# c64-uni-cart-rev4.net
KiCad netlist of a schematic drawn in EAGLE
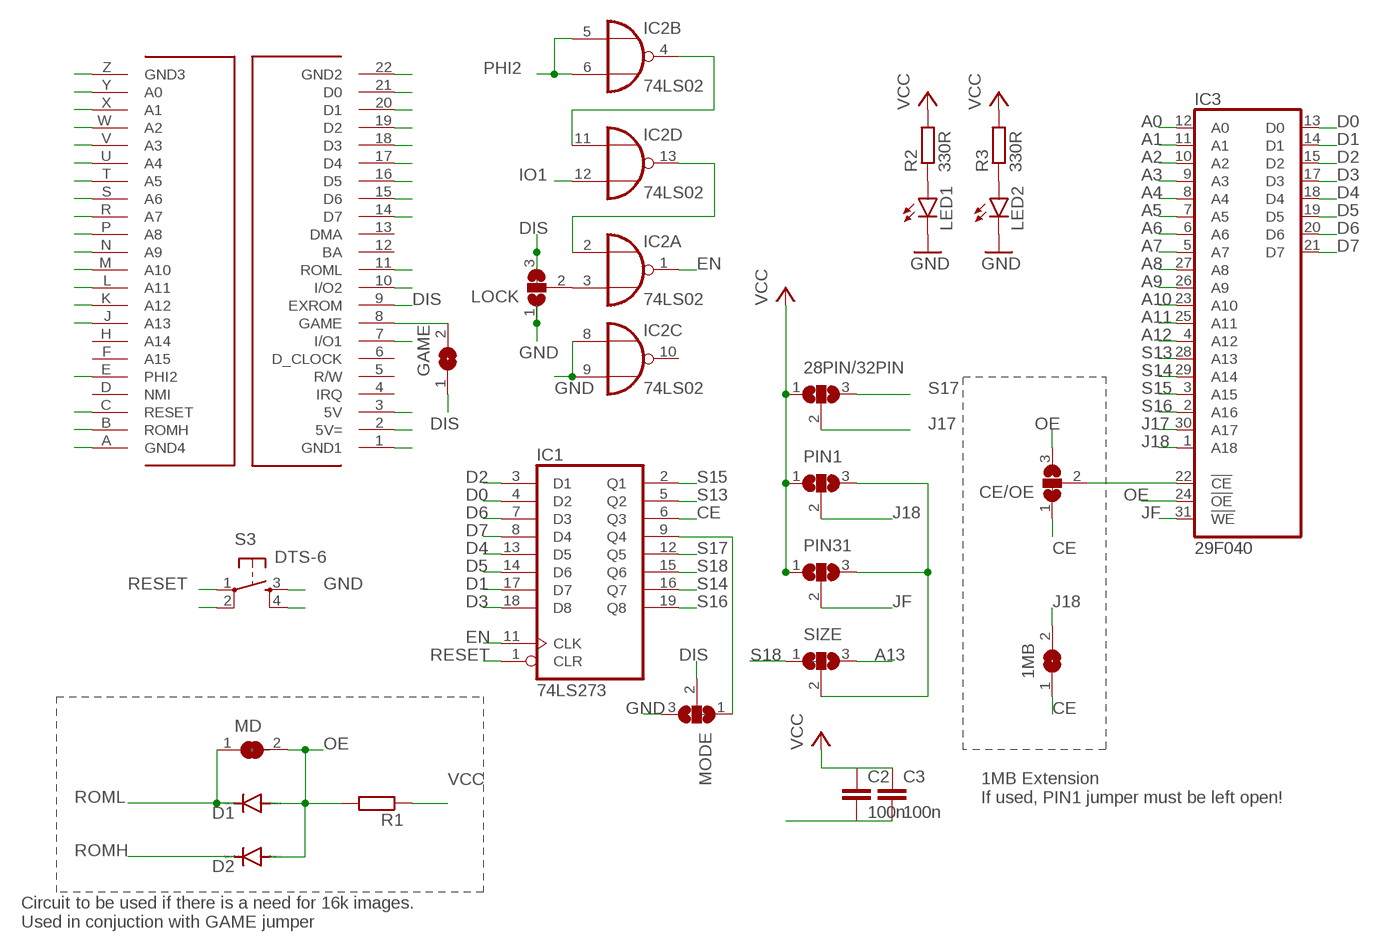
[diagram p0: schematic, sheet 1]

(export (version "E")
  (design (tool "Eeschema 10.0.6"))
  (components
    (comp (ref "1MB") (value "SJ") (footprint "eagle-import:SJ") (libsource (lib "eagle-import") (part "SJ")))
    (comp (ref "28PIN/32PIN")
      (value "SJ2W")
      (footprint "eagle-import:SJ_2")
      (libsource (lib "eagle-import") (part "SJ2W"))
    )
    (comp (ref "C2")
      (value "100n")
      (footprint "eagle-import:C025-024X044")
      (libsource (lib "eagle-import") (part "C-EU025-024X044"))
    )
    (comp (ref "C3")
      (value "100n")
      (footprint "eagle-import:C025-024X044")
      (libsource (lib "eagle-import") (part "C-EU025-024X044"))
    )
    (comp (ref "CE/OE")
      (value "SJ2W")
      (footprint "eagle-import:SJ_2")
      (libsource (lib "eagle-import") (part "SJ2W"))
    )
    (comp (ref "D1")
      (value "DIODE-MINIMELF")
      (footprint "eagle-import:MINIMELF")
      (libsource (lib "eagle-import") (part "DIODE-MINIMELF"))
    )
    (comp (ref "D2")
      (value "DIODE-MINIMELF")
      (footprint "eagle-import:MINIMELF")
      (libsource (lib "eagle-import") (part "DIODE-MINIMELF"))
    )
    (comp (ref "GAME")
      (value "SJ")
      (footprint "eagle-import:SJ")
      (libsource (lib "eagle-import") (part "SJ"))
    )
    (comp (ref "IC1")
      (value "74LS273")
      (footprint "eagle-import:DIL20")
      (libsource (lib "eagle-import") (part "74273NHCT"))
    )
    (comp (ref "IC2")
      (value "74LS02")
      (footprint "eagle-import:DIL14")
      (libsource (lib "eagle-import") (part "7402NLS"))
    )
    (comp (ref "IC3")
      (value "29F040")
      (footprint "eagle-import:DIL32-6")
      (libsource (lib "eagle-import") (part "AM29F040N"))
    )
    (comp (ref "LED1")
      (value "LED3MM")
      (footprint "eagle-import:LED3MM")
      (libsource (lib "eagle-import") (part "LED3MM"))
    )
    (comp (ref "LED2")
      (value "LED3MM")
      (footprint "eagle-import:LED3MM")
      (libsource (lib "eagle-import") (part "LED3MM"))
    )
    (comp (ref "LOCK")
      (value "SJ2W")
      (footprint "eagle-import:SJ_2")
      (libsource (lib "eagle-import") (part "SJ2W"))
    )
    (comp (ref "MD") (value "SJ") (footprint "eagle-import:SJ") (libsource (lib "eagle-import") (part "SJ")))
    (comp (ref "MODE")
      (value "SJ2W")
      (footprint "eagle-import:SJ_2")
      (libsource (lib "eagle-import") (part "SJ2W"))
    )
    (comp (ref "PIN1")
      (value "SJ2W")
      (footprint "eagle-import:SJ_2")
      (libsource (lib "eagle-import") (part "SJ2W"))
    )
    (comp (ref "PIN31")
      (value "SJ2W")
      (footprint "eagle-import:SJ_2")
      (libsource (lib "eagle-import") (part "SJ2W"))
    )
    (comp (ref "R1")
      (value "R-EU_R1206")
      (footprint "eagle-import:R1206")
      (libsource (lib "eagle-import") (part "R-EU_R1206"))
    )
    (comp (ref "R2")
      (value "330R")
      (footprint "eagle-import:R0805")
      (libsource (lib "eagle-import") (part "R-EU_R0805"))
    )
    (comp (ref "R3")
      (value "330R")
      (footprint "eagle-import:R0805")
      (libsource (lib "eagle-import") (part "R-EU_R0805"))
    )
    (comp (ref "S3")
      (value "DTS-6")
      (footprint "eagle-import:DTS-6")
      (libsource (lib "eagle-import") (part "DTS-6"))
    )
    (comp (ref "SIZE")
      (value "SJ2W")
      (footprint "eagle-import:SJ_2")
      (libsource (lib "eagle-import") (part "SJ2W"))
    )
    (comp (ref "U$1")
      (value "C64_CARTRIDGESTUMPY")
      (footprint "eagle-import:C64_STUMPY")
      (libsource (lib "eagle-import") (part "C64_CARTRIDGESTUMPY"))
    )
  )
  (nets
    (net (code "1") (name "/A0") (class "Default")
      (node (ref "IC3") (pin "12") (pinfunction "A0_12") (pintype "input"))
      (node (ref "U$1") (pin "Y") (pinfunction "A0_Y") (pintype "bidirectional"))
    )
    (net (code "2") (name "/A1") (class "Default")
      (node (ref "IC3") (pin "11") (pinfunction "A1_11") (pintype "input"))
      (node (ref "U$1") (pin "X") (pinfunction "A1_X") (pintype "bidirectional"))
    )
    (net (code "3") (name "/A2") (class "Default")
      (node (ref "IC3") (pin "10") (pinfunction "A2_10") (pintype "input"))
      (node (ref "U$1") (pin "W") (pinfunction "A2_W") (pintype "bidirectional"))
    )
    (net (code "4") (name "/A3") (class "Default")
      (node (ref "IC3") (pin "9") (pinfunction "A3_9") (pintype "input"))
      (node (ref "U$1") (pin "V") (pinfunction "A3_V") (pintype "bidirectional"))
    )
    (net (code "5") (name "/A4") (class "Default")
      (node (ref "IC3") (pin "8") (pinfunction "A4_8") (pintype "input"))
      (node (ref "U$1") (pin "U") (pinfunction "A4_U") (pintype "bidirectional"))
    )
    (net (code "6") (name "/A5") (class "Default")
      (node (ref "IC3") (pin "7") (pinfunction "A5_7") (pintype "input"))
      (node (ref "U$1") (pin "T") (pinfunction "A5_T") (pintype "bidirectional"))
    )
    (net (code "7") (name "/A6") (class "Default")
      (node (ref "IC3") (pin "6") (pinfunction "A6_6") (pintype "input"))
      (node (ref "U$1") (pin "S") (pinfunction "A6_S") (pintype "bidirectional"))
    )
    (net (code "8") (name "/A7") (class "Default")
      (node (ref "IC3") (pin "5") (pinfunction "A7_5") (pintype "input"))
      (node (ref "U$1") (pin "R") (pinfunction "A7_R") (pintype "bidirectional"))
    )
    (net (code "9") (name "/A8") (class "Default")
      (node (ref "IC3") (pin "27") (pinfunction "A8_27") (pintype "input"))
      (node (ref "U$1") (pin "P") (pinfunction "A8_P") (pintype "bidirectional"))
    )
    (net (code "10") (name "/A9") (class "Default")
      (node (ref "IC3") (pin "26") (pinfunction "A9_26") (pintype "input"))
      (node (ref "U$1") (pin "N") (pinfunction "A9_N") (pintype "bidirectional"))
    )
    (net (code "11") (name "/A10") (class "Default")
      (node (ref "IC3") (pin "23") (pinfunction "A10_23") (pintype "input"))
      (node (ref "U$1") (pin "M") (pinfunction "A10_M") (pintype "bidirectional"))
    )
    (net (code "12") (name "/A11") (class "Default")
      (node (ref "IC3") (pin "25") (pinfunction "A11_25") (pintype "input"))
      (node (ref "U$1") (pin "L") (pinfunction "A11_L") (pintype "bidirectional"))
    )
    (net (code "13") (name "/A12") (class "Default")
      (node (ref "IC3") (pin "4") (pinfunction "A12_4") (pintype "input"))
      (node (ref "U$1") (pin "K") (pinfunction "A12_K") (pintype "bidirectional"))
    )
    (net (code "14") (name "/A13") (class "Default")
      (node (ref "SIZE") (pin "3") (pinfunction "3_3") (pintype "passive"))
      (node (ref "U$1") (pin "J") (pinfunction "A13_J") (pintype "bidirectional"))
    )
    (net (code "15") (name "/CE") (class "Default")
      (node (ref "1MB") (pin "1") (pinfunction "1_1") (pintype "passive"))
      (node (ref "CE/OE") (pin "1") (pinfunction "1_1") (pintype "passive"))
      (node (ref "IC1") (pin "6") (pinfunction "Q3_6") (pintype "output"))
    )
    (net (code "16") (name "/D0") (class "Default")
      (node (ref "IC1") (pin "4") (pinfunction "D2_4") (pintype "input"))
      (node (ref "IC3") (pin "13") (pinfunction "D0_13") (pintype "tri_state"))
      (node (ref "U$1") (pin "21") (pinfunction "D0_21") (pintype "bidirectional"))
    )
    (net (code "17") (name "/D1") (class "Default")
      (node (ref "IC1") (pin "17") (pinfunction "D7_17") (pintype "input"))
      (node (ref "IC3") (pin "14") (pinfunction "D1_14") (pintype "tri_state"))
      (node (ref "U$1") (pin "20") (pinfunction "D1_20") (pintype "bidirectional"))
    )
    (net (code "18") (name "/D2") (class "Default")
      (node (ref "IC1") (pin "3") (pinfunction "D1_3") (pintype "input"))
      (node (ref "IC3") (pin "15") (pinfunction "D2_15") (pintype "tri_state"))
      (node (ref "U$1") (pin "19") (pinfunction "D2_19") (pintype "bidirectional"))
    )
    (net (code "19") (name "/D3") (class "Default")
      (node (ref "IC1") (pin "18") (pinfunction "D8_18") (pintype "input"))
      (node (ref "IC3") (pin "17") (pinfunction "D3_17") (pintype "tri_state"))
      (node (ref "U$1") (pin "18") (pinfunction "D3_18") (pintype "bidirectional"))
    )
    (net (code "20") (name "/D4") (class "Default")
      (node (ref "IC1") (pin "13") (pinfunction "D5_13") (pintype "input"))
      (node (ref "IC3") (pin "18") (pinfunction "D4_18") (pintype "tri_state"))
      (node (ref "U$1") (pin "17") (pinfunction "D4_17") (pintype "bidirectional"))
    )
    (net (code "21") (name "/D5") (class "Default")
      (node (ref "IC1") (pin "14") (pinfunction "D6_14") (pintype "input"))
      (node (ref "IC3") (pin "19") (pinfunction "D5_19") (pintype "tri_state"))
      (node (ref "U$1") (pin "16") (pinfunction "D5_16") (pintype "bidirectional"))
    )
    (net (code "22") (name "/D6") (class "Default")
      (node (ref "IC1") (pin "7") (pinfunction "D3_7") (pintype "input"))
      (node (ref "IC3") (pin "20") (pinfunction "D6_20") (pintype "tri_state"))
      (node (ref "U$1") (pin "15") (pinfunction "D6_15") (pintype "bidirectional"))
    )
    (net (code "23") (name "/D7") (class "Default")
      (node (ref "IC1") (pin "8") (pinfunction "D4_8") (pintype "input"))
      (node (ref "IC3") (pin "21") (pinfunction "D7_21") (pintype "tri_state"))
      (node (ref "U$1") (pin "14") (pinfunction "D7_14") (pintype "bidirectional"))
    )
    (net (code "24") (name "/DIS") (class "Default")
      (node (ref "GAME") (pin "1") (pinfunction "1_1") (pintype "passive"))
      (node (ref "LOCK") (pin "3") (pinfunction "3_3") (pintype "passive"))
      (node (ref "MODE") (pin "2") (pinfunction "2_2") (pintype "passive"))
      (node (ref "U$1") (pin "9") (pinfunction "EXROM_9") (pintype "bidirectional"))
    )
    (net (code "25") (name "/EN") (class "Default")
      (node (ref "IC1") (pin "11") (pinfunction "CLK_11") (pintype "input"))
      (node (ref "IC2") (pin "1") (pinfunction "O_1") (pintype "output"))
    )
    (net (code "26") (name "/IO1") (class "Default")
      (node (ref "IC2") (pin "12") (pinfunction "I1_12") (pintype "input"))
      (node (ref "U$1") (pin "7") (pinfunction "I/O1_7") (pintype "bidirectional"))
    )
    (net (code "27") (name "/J17") (class "Default")
      (node (ref "28PIN/32PIN") (pin "2") (pinfunction "2_2") (pintype "passive"))
      (node (ref "IC3") (pin "30") (pinfunction "A17_30") (pintype "input"))
    )
    (net (code "28") (name "/J18") (class "Default")
      (node (ref "1MB") (pin "2") (pinfunction "2_2") (pintype "passive"))
      (node (ref "IC3") (pin "1") (pinfunction "A18_1") (pintype "input"))
      (node (ref "PIN1") (pin "2") (pinfunction "2_2") (pintype "passive"))
    )
    (net (code "29") (name "/JF") (class "Default")
      (node (ref "IC3") (pin "31") (pinfunction "~{WE}_31") (pintype "input"))
      (node (ref "PIN31") (pin "2") (pinfunction "2_2") (pintype "passive"))
    )
    (net (code "30") (name "/OE") (class "Default")
      (node (ref "CE/OE") (pin "3") (pinfunction "3_3") (pintype "passive"))
      (node (ref "D1") (pin "A") (pinfunction "A_A") (pintype "passive"))
      (node (ref "D2") (pin "A") (pinfunction "A_A") (pintype "passive"))
      (node (ref "IC3") (pin "24") (pinfunction "~{OE}_24") (pintype "input"))
      (node (ref "MD") (pin "2") (pinfunction "2_2") (pintype "passive"))
      (node (ref "R1") (pin "2") (pinfunction "2_2") (pintype "passive"))
    )
    (net (code "31") (name "/PHI2") (class "Default")
      (node (ref "IC2") (pin "5") (pinfunction "I0_5") (pintype "input"))
      (node (ref "IC2") (pin "6") (pinfunction "I1_6") (pintype "input"))
      (node (ref "U$1") (pin "E") (pinfunction "PHI2_E") (pintype "bidirectional"))
    )
    (net (code "32") (name "/RESET") (class "Default")
      (node (ref "IC1") (pin "1") (pinfunction "CLR_1") (pintype "input"))
      (node (ref "S3") (pin "1") (pinfunction "1_1") (pintype "passive"))
      (node (ref "S3") (pin "2") (pinfunction "2_2") (pintype "passive"))
      (node (ref "U$1") (pin "C") (pinfunction "RESET_C") (pintype "bidirectional"))
    )
    (net (code "33") (name "/ROMH") (class "Default")
      (node (ref "D2") (pin "C") (pinfunction "C_C") (pintype "passive"))
      (node (ref "U$1") (pin "B") (pinfunction "ROMH_B") (pintype "bidirectional"))
    )
    (net (code "34") (name "/ROML") (class "Default")
      (node (ref "D1") (pin "C") (pinfunction "C_C") (pintype "passive"))
      (node (ref "MD") (pin "1") (pinfunction "1_1") (pintype "passive"))
      (node (ref "U$1") (pin "11") (pinfunction "ROML_11") (pintype "bidirectional"))
    )
    (net (code "35") (name "/S13") (class "Default")
      (node (ref "IC1") (pin "5") (pinfunction "Q2_5") (pintype "output"))
      (node (ref "IC3") (pin "28") (pinfunction "A13_28") (pintype "input"))
    )
    (net (code "36") (name "/S14") (class "Default")
      (node (ref "IC1") (pin "16") (pinfunction "Q7_16") (pintype "output"))
      (node (ref "IC3") (pin "29") (pinfunction "A14_29") (pintype "input"))
    )
    (net (code "37") (name "/S15") (class "Default")
      (node (ref "IC1") (pin "2") (pinfunction "Q1_2") (pintype "output"))
      (node (ref "IC3") (pin "3") (pinfunction "A15_3") (pintype "input"))
    )
    (net (code "38") (name "/S16") (class "Default")
      (node (ref "IC1") (pin "19") (pinfunction "Q8_19") (pintype "output"))
      (node (ref "IC3") (pin "2") (pinfunction "A16_2") (pintype "input"))
    )
    (net (code "39") (name "/S17") (class "Default")
      (node (ref "28PIN/32PIN") (pin "3") (pinfunction "3_3") (pintype "passive"))
      (node (ref "IC1") (pin "12") (pinfunction "Q5_12") (pintype "output"))
    )
    (net (code "40") (name "/S18") (class "Default")
      (node (ref "IC1") (pin "15") (pinfunction "Q6_15") (pintype "output"))
      (node (ref "SIZE") (pin "1") (pinfunction "1_1") (pintype "passive"))
    )
    (net (code "41") (name "GND") (class "Default")
      (node (ref "C2") (pin "2") (pinfunction "2_2") (pintype "passive"))
      (node (ref "C3") (pin "2") (pinfunction "2_2") (pintype "passive"))
      (node (ref "IC2") (pin "8") (pinfunction "I0_8") (pintype "input"))
      (node (ref "IC2") (pin "9") (pinfunction "I1_9") (pintype "input"))
      (node (ref "LED1") (pin "K") (pinfunction "C_K") (pintype "passive"))
      (node (ref "LED2") (pin "K") (pinfunction "C_K") (pintype "passive"))
      (node (ref "LOCK") (pin "1") (pinfunction "1_1") (pintype "passive"))
      (node (ref "MODE") (pin "3") (pinfunction "3_3") (pintype "passive"))
      (node (ref "S3") (pin "3") (pinfunction "3_3") (pintype "passive"))
      (node (ref "S3") (pin "4") (pinfunction "4_4") (pintype "passive"))
      (node (ref "U$1") (pin "1") (pinfunction "GND1_1") (pintype "bidirectional"))
      (node (ref "U$1") (pin "22") (pinfunction "GND2_22") (pintype "bidirectional"))
      (node (ref "U$1") (pin "A") (pinfunction "GND4_A") (pintype "bidirectional"))
      (node (ref "U$1") (pin "Z") (pinfunction "GND3_Z") (pintype "bidirectional"))
    )
    (net (code "42") (name "Net-(IC1A-Q4)") (class "Default")
      (node (ref "IC1") (pin "9") (pinfunction "Q4_9") (pintype "output"))
      (node (ref "MODE") (pin "1") (pinfunction "1_1") (pintype "passive"))
    )
    (net (code "43") (name "Net-(IC2A-I0)") (class "Default")
      (node (ref "IC2") (pin "13") (pinfunction "O_13") (pintype "output"))
      (node (ref "IC2") (pin "2") (pinfunction "I0_2") (pintype "input"))
    )
    (net (code "44") (name "Net-(IC2A-I1)") (class "Default")
      (node (ref "IC2") (pin "3") (pinfunction "I1_3") (pintype "input"))
      (node (ref "LOCK") (pin "2") (pinfunction "2_2") (pintype "passive"))
    )
    (net (code "45") (name "Net-(IC2B-O)") (class "Default")
      (node (ref "IC2") (pin "11") (pinfunction "I0_11") (pintype "input"))
      (node (ref "IC2") (pin "4") (pinfunction "O_4") (pintype "output"))
    )
    (net (code "46") (name "Net-(IC3A-~{CE})") (class "Default")
      (node (ref "CE/OE") (pin "2") (pinfunction "2_2") (pintype "passive"))
      (node (ref "IC3") (pin "22") (pinfunction "~{CE}_22") (pintype "input"))
    )
    (net (code "47") (name "Net-(LED1-PadA)") (class "Default")
      (node (ref "LED1") (pin "A") (pinfunction "A_A") (pintype "passive"))
      (node (ref "R2") (pin "1") (pinfunction "1_1") (pintype "passive"))
    )
    (net (code "48") (name "Net-(LED2-PadA)") (class "Default")
      (node (ref "LED2") (pin "A") (pinfunction "A_A") (pintype "passive"))
      (node (ref "R3") (pin "1") (pinfunction "1_1") (pintype "passive"))
    )
    (net (code "49") (name "Net-(PIN1-Pad3)") (class "Default")
      (node (ref "PIN1") (pin "3") (pinfunction "3_3") (pintype "passive"))
      (node (ref "PIN31") (pin "3") (pinfunction "3_3") (pintype "passive"))
      (node (ref "SIZE") (pin "2") (pinfunction "2_2") (pintype "passive"))
    )
    (net (code "50") (name "Net-(U$1-GAME)") (class "Default")
      (node (ref "GAME") (pin "2") (pinfunction "2_2") (pintype "passive"))
      (node (ref "U$1") (pin "8") (pinfunction "GAME_8") (pintype "bidirectional"))
    )
    (net (code "51") (name "VCC") (class "Default")
      (node (ref "28PIN/32PIN") (pin "1") (pinfunction "1_1") (pintype "passive"))
      (node (ref "C2") (pin "1") (pinfunction "1_1") (pintype "passive"))
      (node (ref "C3") (pin "1") (pinfunction "1_1") (pintype "passive"))
      (node (ref "PIN1") (pin "1") (pinfunction "1_1") (pintype "passive"))
      (node (ref "PIN31") (pin "1") (pinfunction "1_1") (pintype "passive"))
      (node (ref "R1") (pin "1") (pinfunction "1_1") (pintype "passive"))
      (node (ref "R2") (pin "2") (pinfunction "2_2") (pintype "passive"))
      (node (ref "R3") (pin "2") (pinfunction "2_2") (pintype "passive"))
      (node (ref "U$1") (pin "2") (pinfunction "5V=_2") (pintype "bidirectional"))
      (node (ref "U$1") (pin "3") (pinfunction "5V_3") (pintype "bidirectional"))
    )
    (net (code "52") (name "unconnected-(IC2C-O-Pad10)") (class "Default")
      (node (ref "IC2") (pin "10") (pinfunction "O_10") (pintype "output"))
    )
    (net (code "53") (name "unconnected-(U$1-A14-PadH)") (class "Default")
      (node (ref "U$1") (pin "H") (pinfunction "A14_H") (pintype "bidirectional"))
    )
    (net (code "54") (name "unconnected-(U$1-A15-PadF)") (class "Default")
      (node (ref "U$1") (pin "F") (pinfunction "A15_F") (pintype "bidirectional"))
    )
    (net (code "55") (name "unconnected-(U$1-BA-Pad12)") (class "Default")
      (node (ref "U$1") (pin "12") (pinfunction "BA_12") (pintype "bidirectional"))
    )
    (net (code "56") (name "unconnected-(U$1-DMA-Pad13)") (class "Default")
      (node (ref "U$1") (pin "13") (pinfunction "DMA_13") (pintype "bidirectional"))
    )
    (net (code "57") (name "unconnected-(U$1-D_CLOCK-Pad6)") (class "Default")
      (node (ref "U$1") (pin "6") (pinfunction "D_CLOCK_6") (pintype "bidirectional"))
    )
    (net (code "58") (name "unconnected-(U$1-IRQ-Pad4)") (class "Default")
      (node (ref "U$1") (pin "4") (pinfunction "IRQ_4") (pintype "bidirectional"))
    )
    (net (code "59") (name "unconnected-(U$1-I{slash}O2-Pad10)") (class "Default")
      (node (ref "U$1") (pin "10") (pinfunction "I/O2_10") (pintype "bidirectional"))
    )
    (net (code "60") (name "unconnected-(U$1-NMI-PadD)") (class "Default")
      (node (ref "U$1") (pin "D") (pinfunction "NMI_D") (pintype "bidirectional"))
    )
    (net (code "61") (name "unconnected-(U$1-R{slash}W-Pad5)") (class "Default")
      (node (ref "U$1") (pin "5") (pinfunction "R/W_5") (pintype "bidirectional"))
    )
  )
)
